# imp_match_v1.net
KiCad netlist of a schematic drawn in Altium Designer
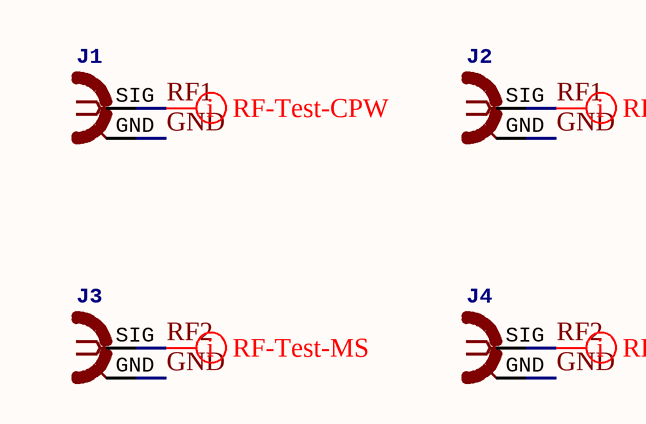
[diagram p0: imp_match_v1.SchDoc]

(export (version "E")
  (design (tool "Eeschema 10.0.6"))
  (components
    (comp (ref "J1")
      (value "SMA 50 Ohm edge")
      (footprint "SMA-OSHPARK-4L-1.6MM")
      (fields (field (name "LIBRARYNAME") "dword1511-connectors"))
      (libsource (lib "wcsng_altium") (part "SMA-OSHPARK-4L-1.6MM"))
    )
    (comp (ref "J2")
      (value "SMA 50 Ohm edge")
      (footprint "SMA-OSHPARK-4L-1.6MM")
      (fields (field (name "LIBRARYNAME") "dword1511-connectors"))
      (libsource (lib "wcsng_altium") (part "SMA-OSHPARK-4L-1.6MM"))
    )
    (comp (ref "J3")
      (value "SMA 50 Ohm edge")
      (footprint "SMA-OSHPARK-4L-1.6MM")
      (fields (field (name "LIBRARYNAME") "dword1511-connectors"))
      (libsource (lib "wcsng_altium") (part "SMA-OSHPARK-4L-1.6MM"))
    )
    (comp (ref "J4")
      (value "SMA 50 Ohm edge")
      (footprint "SMA-OSHPARK-4L-1.6MM")
      (fields (field (name "LIBRARYNAME") "dword1511-connectors"))
      (libsource (lib "wcsng_altium") (part "SMA-OSHPARK-4L-1.6MM"))
    )
  )
  (nets
    (net (code "1") (name "/GND") (class "Default")
      (node (ref "J1") (pin "GND") (pinfunction "GND_GND") (pintype "passive"))
      (node (ref "J2") (pin "GND") (pinfunction "GND_GND") (pintype "passive"))
      (node (ref "J3") (pin "GND") (pinfunction "GND_GND") (pintype "passive"))
      (node (ref "J4") (pin "GND") (pinfunction "GND_GND") (pintype "passive"))
    )
    (net (code "2") (name "/RF1") (class "Default")
      (node (ref "J1") (pin "SIG") (pinfunction "SIG_SIG") (pintype "passive"))
      (node (ref "J2") (pin "SIG") (pinfunction "SIG_SIG") (pintype "passive"))
    )
    (net (code "3") (name "/RF2") (class "Default")
      (node (ref "J3") (pin "SIG") (pinfunction "SIG_SIG") (pintype "passive"))
      (node (ref "J4") (pin "SIG") (pinfunction "SIG_SIG") (pintype "passive"))
    )
  )
)
